# NanoConnectionBoard.net
KiCad netlist of a schematic drawn in EAGLE
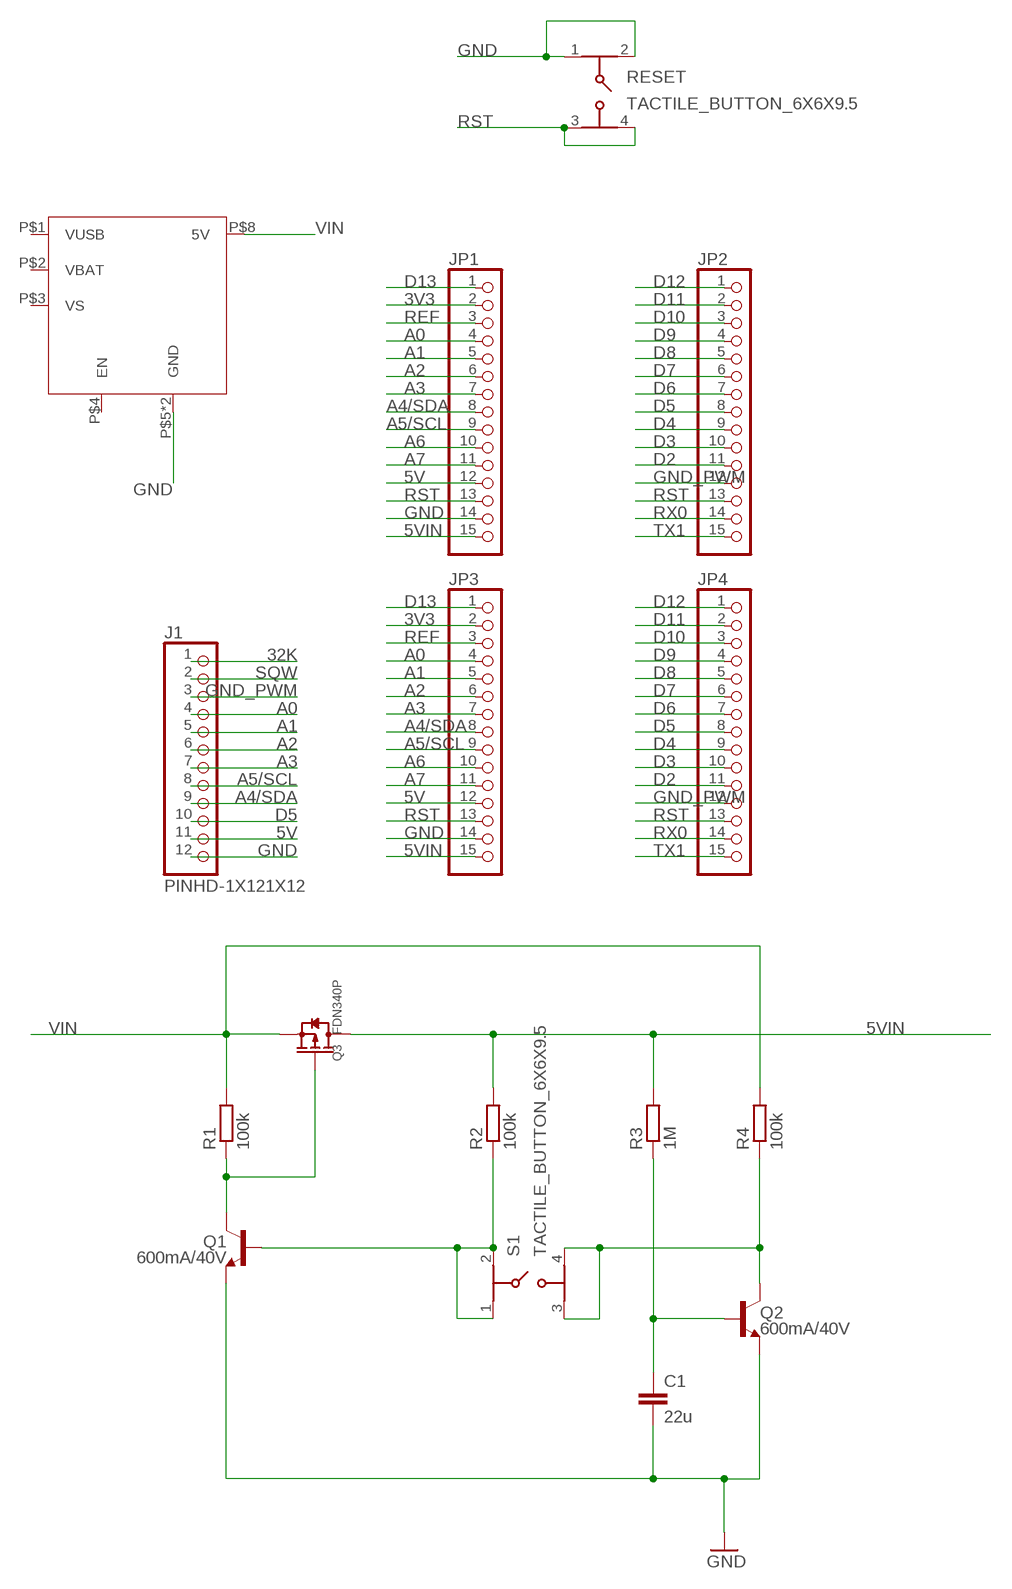
[diagram p0: schematic, sheet 1]

(export (version "E")
  (design (tool "Eeschema 10.0.6"))
  (components
    (comp (ref "C1")
      (value "22u")
      (footprint "eagle-import:C1210K")
      (libsource (lib "eagle-import") (part "C-EUC1210K"))
    )
    (comp (ref "J1")
      (value "PINHD-1X121X12")
      (footprint "eagle-import:1X12")
      (libsource (lib "eagle-import") (part "PINHD-1X121X12"))
    )
    (comp (ref "JP1")
      (value "PINHD-1X15-CB")
      (footprint "eagle-import:1X15-CB")
      (libsource (lib "eagle-import") (part "PINHD-1X15-CB"))
    )
    (comp (ref "JP2")
      (value "PINHD-1X15-CB")
      (footprint "eagle-import:1X15-CB")
      (libsource (lib "eagle-import") (part "PINHD-1X15-CB"))
    )
    (comp (ref "JP3")
      (value "PINHD-1X15-CB")
      (footprint "eagle-import:1X15-CB")
      (libsource (lib "eagle-import") (part "PINHD-1X15-CB"))
    )
    (comp (ref "JP4")
      (value "PINHD-1X15-CB")
      (footprint "eagle-import:1X15-CB")
      (libsource (lib "eagle-import") (part "PINHD-1X15-CB"))
    )
    (comp (ref "Q1")
      (value "600mA/40V")
      (footprint "eagle-import:TO-92")
      (libsource (lib "eagle-import") (part "TRANS_NPN-P2N2222A"))
    )
    (comp (ref "Q2")
      (value "600mA/40V")
      (footprint "eagle-import:TO-92")
      (libsource (lib "eagle-import") (part "TRANS_NPN-P2N2222A"))
    )
    (comp (ref "Q3")
      (value "FDN340P")
      (footprint "eagle-import:SOT-23")
      (libsource (lib "eagle-import") (part "SMD-MOSFET-P-CH-20V-2A-FDN340P(SOT-23)"))
    )
    (comp (ref "R1")
      (value "100k")
      (footprint "eagle-import:R0603")
      (libsource (lib "eagle-import") (part "R-EU_R0603"))
    )
    (comp (ref "R2")
      (value "100k")
      (footprint "eagle-import:R0603")
      (libsource (lib "eagle-import") (part "R-EU_R0603"))
    )
    (comp (ref "R3")
      (value "1M")
      (footprint "eagle-import:R0603")
      (libsource (lib "eagle-import") (part "R-EU_R0603"))
    )
    (comp (ref "R4")
      (value "100k")
      (footprint "eagle-import:R0603")
      (libsource (lib "eagle-import") (part "R-EU_R0603"))
    )
    (comp (ref "RESET")
      (value "TACTILE_BUTTON_6X6X9.5")
      (footprint "eagle-import:TACTILE_SWITCH_PTH_6.0MM")
      (libsource (lib "eagle-import") (part "TACTILE_BUTTON_6X6X9.5"))
    )
    (comp (ref "S1")
      (value "TACTILE_BUTTON_6X6X9.5")
      (footprint "eagle-import:TACTILE_SWITCH_PTH_6.0MM")
      (libsource (lib "eagle-import") (part "TACTILE_BUTTON_6X6X9.5"))
    )
    (comp (ref "U$1")
      (value "ADAFRUIT_POWERBOOST_1000C")
      (footprint "eagle-import:ADAFRUIT_POWERBOOST_1000C")
      (libsource (lib "eagle-import") (part "ADAFRUIT_POWERBOOST_1000C"))
    )
  )
  (nets
    (net (code "1") (name "/3V3") (class "Default")
      (node (ref "JP1") (pin "2") (pinfunction "2_2") (pintype "passive"))
      (node (ref "JP3") (pin "2") (pinfunction "2_2") (pintype "passive"))
    )
    (net (code "2") (name "/5V") (class "Default")
      (node (ref "J1") (pin "11") (pinfunction "11_11") (pintype "passive"))
      (node (ref "JP1") (pin "12") (pinfunction "12_12") (pintype "passive"))
      (node (ref "JP3") (pin "12") (pinfunction "12_12") (pintype "passive"))
    )
    (net (code "3") (name "/5VIN") (class "Default")
      (node (ref "JP1") (pin "15") (pinfunction "15_15") (pintype "passive"))
      (node (ref "JP3") (pin "15") (pinfunction "15_15") (pintype "passive"))
      (node (ref "Q3") (pin "3") (pinfunction "D_3") (pintype "passive"))
      (node (ref "R2") (pin "2") (pinfunction "2_2") (pintype "passive"))
      (node (ref "R3") (pin "2") (pinfunction "2_2") (pintype "passive"))
    )
    (net (code "4") (name "/32K") (class "Default")
      (node (ref "J1") (pin "1") (pinfunction "1_1") (pintype "passive"))
    )
    (net (code "5") (name "/A0") (class "Default")
      (node (ref "J1") (pin "4") (pinfunction "4_4") (pintype "passive"))
      (node (ref "JP1") (pin "4") (pinfunction "4_4") (pintype "passive"))
      (node (ref "JP3") (pin "4") (pinfunction "4_4") (pintype "passive"))
    )
    (net (code "6") (name "/A1") (class "Default")
      (node (ref "J1") (pin "5") (pinfunction "5_5") (pintype "passive"))
      (node (ref "JP1") (pin "5") (pinfunction "5_5") (pintype "passive"))
      (node (ref "JP3") (pin "5") (pinfunction "5_5") (pintype "passive"))
    )
    (net (code "7") (name "/A2") (class "Default")
      (node (ref "J1") (pin "6") (pinfunction "6_6") (pintype "passive"))
      (node (ref "JP1") (pin "6") (pinfunction "6_6") (pintype "passive"))
      (node (ref "JP3") (pin "6") (pinfunction "6_6") (pintype "passive"))
    )
    (net (code "8") (name "/A3") (class "Default")
      (node (ref "J1") (pin "7") (pinfunction "7_7") (pintype "passive"))
      (node (ref "JP1") (pin "7") (pinfunction "7_7") (pintype "passive"))
      (node (ref "JP3") (pin "7") (pinfunction "7_7") (pintype "passive"))
    )
    (net (code "9") (name "/A4{slash}SDA") (class "Default")
      (node (ref "J1") (pin "9") (pinfunction "9_9") (pintype "passive"))
      (node (ref "JP1") (pin "8") (pinfunction "8_8") (pintype "passive"))
      (node (ref "JP3") (pin "8") (pinfunction "8_8") (pintype "passive"))
    )
    (net (code "10") (name "/A5{slash}SCL") (class "Default")
      (node (ref "J1") (pin "8") (pinfunction "8_8") (pintype "passive"))
      (node (ref "JP1") (pin "9") (pinfunction "9_9") (pintype "passive"))
      (node (ref "JP3") (pin "9") (pinfunction "9_9") (pintype "passive"))
    )
    (net (code "11") (name "/A6") (class "Default")
      (node (ref "JP1") (pin "10") (pinfunction "10_10") (pintype "passive"))
      (node (ref "JP3") (pin "10") (pinfunction "10_10") (pintype "passive"))
    )
    (net (code "12") (name "/A7") (class "Default")
      (node (ref "JP1") (pin "11") (pinfunction "11_11") (pintype "passive"))
      (node (ref "JP3") (pin "11") (pinfunction "11_11") (pintype "passive"))
    )
    (net (code "13") (name "/D2") (class "Default")
      (node (ref "JP2") (pin "11") (pinfunction "11_11") (pintype "passive"))
      (node (ref "JP4") (pin "11") (pinfunction "11_11") (pintype "passive"))
    )
    (net (code "14") (name "/D3") (class "Default")
      (node (ref "JP2") (pin "10") (pinfunction "10_10") (pintype "passive"))
      (node (ref "JP4") (pin "10") (pinfunction "10_10") (pintype "passive"))
    )
    (net (code "15") (name "/D4") (class "Default")
      (node (ref "JP2") (pin "9") (pinfunction "9_9") (pintype "passive"))
      (node (ref "JP4") (pin "9") (pinfunction "9_9") (pintype "passive"))
    )
    (net (code "16") (name "/D5") (class "Default")
      (node (ref "J1") (pin "10") (pinfunction "10_10") (pintype "passive"))
      (node (ref "JP2") (pin "8") (pinfunction "8_8") (pintype "passive"))
      (node (ref "JP4") (pin "8") (pinfunction "8_8") (pintype "passive"))
    )
    (net (code "17") (name "/D6") (class "Default")
      (node (ref "JP2") (pin "7") (pinfunction "7_7") (pintype "passive"))
      (node (ref "JP4") (pin "7") (pinfunction "7_7") (pintype "passive"))
    )
    (net (code "18") (name "/D7") (class "Default")
      (node (ref "JP2") (pin "6") (pinfunction "6_6") (pintype "passive"))
      (node (ref "JP4") (pin "6") (pinfunction "6_6") (pintype "passive"))
    )
    (net (code "19") (name "/D8") (class "Default")
      (node (ref "JP2") (pin "5") (pinfunction "5_5") (pintype "passive"))
      (node (ref "JP4") (pin "5") (pinfunction "5_5") (pintype "passive"))
    )
    (net (code "20") (name "/D9") (class "Default")
      (node (ref "JP2") (pin "4") (pinfunction "4_4") (pintype "passive"))
      (node (ref "JP4") (pin "4") (pinfunction "4_4") (pintype "passive"))
    )
    (net (code "21") (name "/D10") (class "Default")
      (node (ref "JP2") (pin "3") (pinfunction "3_3") (pintype "passive"))
      (node (ref "JP4") (pin "3") (pinfunction "3_3") (pintype "passive"))
    )
    (net (code "22") (name "/D11") (class "Default")
      (node (ref "JP2") (pin "2") (pinfunction "2_2") (pintype "passive"))
      (node (ref "JP4") (pin "2") (pinfunction "2_2") (pintype "passive"))
    )
    (net (code "23") (name "/D12") (class "Default")
      (node (ref "JP2") (pin "1") (pinfunction "1_1") (pintype "passive"))
      (node (ref "JP4") (pin "1") (pinfunction "1_1") (pintype "passive"))
    )
    (net (code "24") (name "/D13") (class "Default")
      (node (ref "JP1") (pin "1") (pinfunction "1_1") (pintype "passive"))
      (node (ref "JP3") (pin "1") (pinfunction "1_1") (pintype "passive"))
    )
    (net (code "25") (name "/GND_PWM") (class "Default")
      (node (ref "J1") (pin "3") (pinfunction "3_3") (pintype "passive"))
      (node (ref "JP2") (pin "12") (pinfunction "12_12") (pintype "passive"))
      (node (ref "JP4") (pin "12") (pinfunction "12_12") (pintype "passive"))
    )
    (net (code "26") (name "/REF") (class "Default")
      (node (ref "JP1") (pin "3") (pinfunction "3_3") (pintype "passive"))
      (node (ref "JP3") (pin "3") (pinfunction "3_3") (pintype "passive"))
    )
    (net (code "27") (name "/RST") (class "Default")
      (node (ref "JP1") (pin "13") (pinfunction "13_13") (pintype "passive"))
      (node (ref "JP2") (pin "13") (pinfunction "13_13") (pintype "passive"))
      (node (ref "JP3") (pin "13") (pinfunction "13_13") (pintype "passive"))
      (node (ref "JP4") (pin "13") (pinfunction "13_13") (pintype "passive"))
      (node (ref "RESET") (pin "3") (pinfunction "2_3") (pintype "passive"))
      (node (ref "RESET") (pin "4") (pinfunction "4_4") (pintype "passive"))
    )
    (net (code "28") (name "/RX0") (class "Default")
      (node (ref "JP2") (pin "14") (pinfunction "14_14") (pintype "passive"))
      (node (ref "JP4") (pin "14") (pinfunction "14_14") (pintype "passive"))
    )
    (net (code "29") (name "/SQW") (class "Default")
      (node (ref "J1") (pin "2") (pinfunction "2_2") (pintype "passive"))
    )
    (net (code "30") (name "/TX1") (class "Default")
      (node (ref "JP2") (pin "15") (pinfunction "15_15") (pintype "passive"))
      (node (ref "JP4") (pin "15") (pinfunction "15_15") (pintype "passive"))
    )
    (net (code "31") (name "/VBAT") (class "Default")
      (node (ref "U$1") (pin "P$2") (pinfunction "VBAT_P$2") (pintype "power_in"))
    )
    (net (code "32") (name "/VIN") (class "Default")
      (node (ref "Q3") (pin "2") (pinfunction "S_2") (pintype "passive"))
      (node (ref "R1") (pin "2") (pinfunction "2_2") (pintype "passive"))
      (node (ref "R4") (pin "2") (pinfunction "2_2") (pintype "passive"))
      (node (ref "U$1") (pin "P$8") (pinfunction "5V_P$8") (pintype "bidirectional"))
    )
    (net (code "33") (name "/VS") (class "Default")
      (node (ref "U$1") (pin "P$3") (pinfunction "VS_P$3") (pintype "power_in"))
    )
    (net (code "34") (name "/VUSB") (class "Default")
      (node (ref "U$1") (pin "P$1") (pinfunction "VUSB_P$1") (pintype "power_in"))
    )
    (net (code "35") (name "GND") (class "Default")
      (node (ref "C1") (pin "2") (pinfunction "2_2") (pintype "passive"))
      (node (ref "J1") (pin "12") (pinfunction "12_12") (pintype "passive"))
      (node (ref "JP1") (pin "14") (pinfunction "14_14") (pintype "passive"))
      (node (ref "JP3") (pin "14") (pinfunction "14_14") (pintype "passive"))
      (node (ref "Q1") (pin "3") (pinfunction "E_3") (pintype "passive"))
      (node (ref "Q2") (pin "3") (pinfunction "E_3") (pintype "passive"))
      (node (ref "RESET") (pin "1") (pinfunction "1_1") (pintype "passive"))
      (node (ref "RESET") (pin "2") (pinfunction "3_2") (pintype "passive"))
      (node (ref "U$1") (pin "P$5") (pinfunction "GND_P$5") (pintype "power_in"))
      (node (ref "U$1") (pin "P$7") (pinfunction "GND_P$7") (pintype "power_in"))
    )
    (net (code "36") (name "Net-(Q1-B)") (class "Default")
      (node (ref "Q1") (pin "2") (pinfunction "B_2") (pintype "passive"))
      (node (ref "R2") (pin "1") (pinfunction "1_1") (pintype "passive"))
      (node (ref "S1") (pin "1") (pinfunction "1_1") (pintype "passive"))
      (node (ref "S1") (pin "2") (pinfunction "3_2") (pintype "passive"))
    )
    (net (code "37") (name "Net-(Q1-C)") (class "Default")
      (node (ref "Q1") (pin "1") (pinfunction "C_1") (pintype "passive"))
      (node (ref "Q3") (pin "1") (pinfunction "G_1") (pintype "passive"))
      (node (ref "R1") (pin "1") (pinfunction "1_1") (pintype "passive"))
    )
    (net (code "38") (name "Net-(Q2-B)") (class "Default")
      (node (ref "C1") (pin "1") (pinfunction "1_1") (pintype "passive"))
      (node (ref "Q2") (pin "2") (pinfunction "B_2") (pintype "passive"))
      (node (ref "R3") (pin "1") (pinfunction "1_1") (pintype "passive"))
    )
    (net (code "39") (name "Net-(Q2-C)") (class "Default")
      (node (ref "Q2") (pin "1") (pinfunction "C_1") (pintype "passive"))
      (node (ref "R4") (pin "1") (pinfunction "1_1") (pintype "passive"))
      (node (ref "S1") (pin "3") (pinfunction "2_3") (pintype "passive"))
      (node (ref "S1") (pin "4") (pinfunction "4_4") (pintype "passive"))
    )
    (net (code "40") (name "unconnected-(U$1-EN-PadP$4)") (class "Default")
      (node (ref "U$1") (pin "P$4") (pinfunction "EN_P$4") (pintype "bidirectional"))
    )
  )
)
